# 8bit_ALU.net
KiCad netlist of a schematic drawn in EAGLE
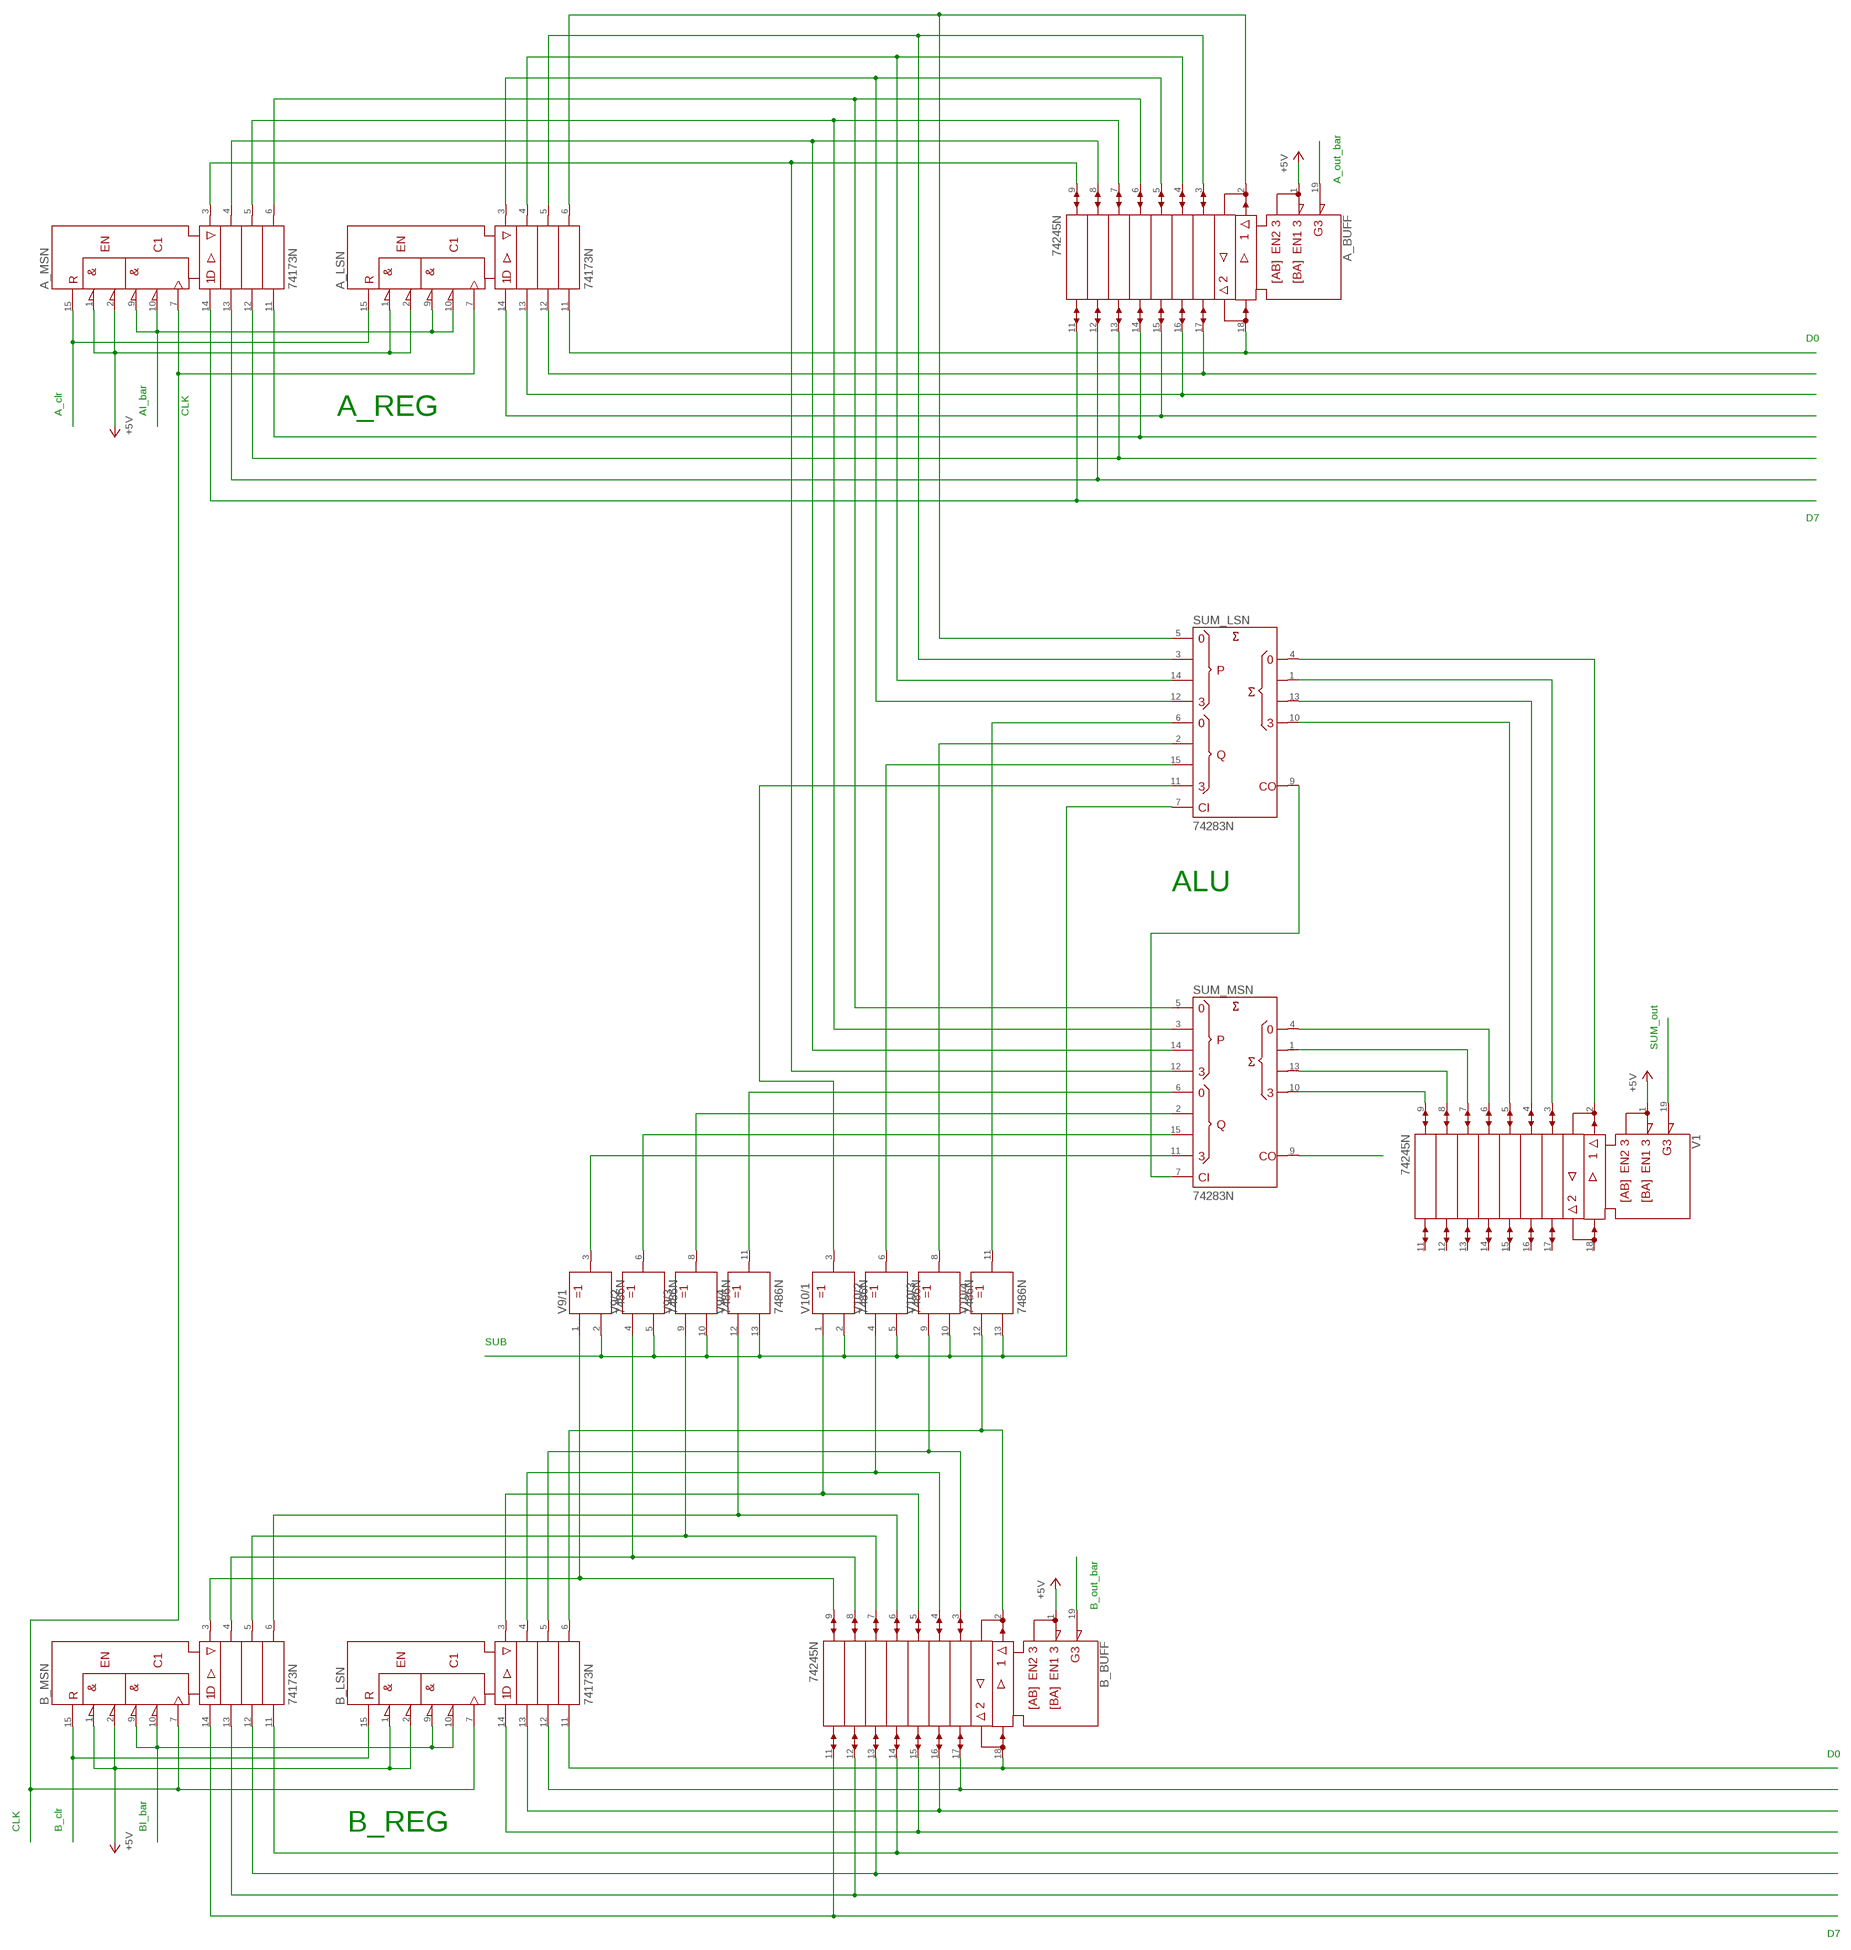
[diagram p0: schematic, sheet 1]

(export (version "E")
  (design (tool "Eeschema 10.0.6"))
  (components
    (comp (ref "A_BUFF")
      (value "74245N")
      (footprint "eagle-import:DIL20")
      (libsource (lib "eagle-import") (part "74245N"))
    )
    (comp (ref "A_LSN")
      (value "74173N")
      (footprint "eagle-import:DIL16")
      (libsource (lib "eagle-import") (part "74173N"))
    )
    (comp (ref "A_MSN")
      (value "74173N")
      (footprint "eagle-import:DIL16")
      (libsource (lib "eagle-import") (part "74173N"))
    )
    (comp (ref "B_BUFF")
      (value "74245N")
      (footprint "eagle-import:DIL20")
      (libsource (lib "eagle-import") (part "74245N"))
    )
    (comp (ref "B_LSN")
      (value "74173N")
      (footprint "eagle-import:DIL16")
      (libsource (lib "eagle-import") (part "74173N"))
    )
    (comp (ref "B_MSN")
      (value "74173N")
      (footprint "eagle-import:DIL16")
      (libsource (lib "eagle-import") (part "74173N"))
    )
    (comp (ref "SUM_LSN")
      (value "74283N")
      (footprint "eagle-import:DIL16")
      (libsource (lib "eagle-import") (part "74283N"))
    )
    (comp (ref "SUM_MSN")
      (value "74283N")
      (footprint "eagle-import:DIL16")
      (libsource (lib "eagle-import") (part "74283N"))
    )
    (comp (ref "V1")
      (value "74245N")
      (footprint "eagle-import:DIL20")
      (libsource (lib "eagle-import") (part "74245N"))
    )
    (comp (ref "V9")
      (value "7486N")
      (footprint "eagle-import:DIL14")
      (libsource (lib "eagle-import") (part "7486N"))
    )
    (comp (ref "V10")
      (value "7486N")
      (footprint "eagle-import:DIL14")
      (libsource (lib "eagle-import") (part "7486N"))
    )
  )
  (nets
    (net (code "1") (name "+5V") (class "Default")
      (node (ref "A_BUFF") (pin "1") (pinfunction "DIR_1") (pintype "input"))
      (node (ref "A_LSN") (pin "1") (pinfunction "M_1") (pintype "input"))
      (node (ref "A_LSN") (pin "2") (pinfunction "N_2") (pintype "input"))
      (node (ref "A_MSN") (pin "1") (pinfunction "M_1") (pintype "input"))
      (node (ref "A_MSN") (pin "2") (pinfunction "N_2") (pintype "input"))
      (node (ref "B_BUFF") (pin "1") (pinfunction "DIR_1") (pintype "input"))
      (node (ref "B_LSN") (pin "1") (pinfunction "M_1") (pintype "input"))
      (node (ref "B_LSN") (pin "2") (pinfunction "N_2") (pintype "input"))
      (node (ref "B_MSN") (pin "1") (pinfunction "M_1") (pintype "input"))
      (node (ref "B_MSN") (pin "2") (pinfunction "N_2") (pintype "input"))
      (node (ref "V1") (pin "1") (pinfunction "DIR_1") (pintype "input"))
    )
    (net (code "2") (name "Net-(A_BUFFC-A1)") (class "Default")
      (node (ref "A_BUFF") (pin "2") (pinfunction "A1_2") (pintype "bidirectional"))
      (node (ref "A_LSN") (pin "6") (pinfunction "4Q_6") (pintype "tri_state"))
      (node (ref "SUM_LSN") (pin "5") (pinfunction "A1_5") (pintype "input"))
    )
    (net (code "3") (name "Net-(A_BUFFC-A2)") (class "Default")
      (node (ref "A_BUFF") (pin "3") (pinfunction "A2_3") (pintype "bidirectional"))
      (node (ref "A_LSN") (pin "5") (pinfunction "3Q_5") (pintype "tri_state"))
      (node (ref "SUM_LSN") (pin "3") (pinfunction "A2_3") (pintype "input"))
    )
    (net (code "4") (name "Net-(A_BUFFC-A3)") (class "Default")
      (node (ref "A_BUFF") (pin "4") (pinfunction "A3_4") (pintype "bidirectional"))
      (node (ref "A_LSN") (pin "4") (pinfunction "2Q_4") (pintype "tri_state"))
      (node (ref "SUM_LSN") (pin "14") (pinfunction "A3_14") (pintype "input"))
    )
    (net (code "5") (name "Net-(A_BUFFC-A4)") (class "Default")
      (node (ref "A_BUFF") (pin "5") (pinfunction "A4_5") (pintype "bidirectional"))
      (node (ref "A_LSN") (pin "3") (pinfunction "1Q_3") (pintype "tri_state"))
      (node (ref "SUM_LSN") (pin "12") (pinfunction "A4_12") (pintype "input"))
    )
    (net (code "6") (name "Net-(A_BUFFC-A5)") (class "Default")
      (node (ref "A_BUFF") (pin "6") (pinfunction "A5_6") (pintype "bidirectional"))
      (node (ref "A_MSN") (pin "6") (pinfunction "4Q_6") (pintype "tri_state"))
      (node (ref "SUM_MSN") (pin "5") (pinfunction "A1_5") (pintype "input"))
    )
    (net (code "7") (name "Net-(A_BUFFC-A6)") (class "Default")
      (node (ref "A_BUFF") (pin "7") (pinfunction "A6_7") (pintype "bidirectional"))
      (node (ref "A_MSN") (pin "5") (pinfunction "3Q_5") (pintype "tri_state"))
      (node (ref "SUM_MSN") (pin "3") (pinfunction "A2_3") (pintype "input"))
    )
    (net (code "8") (name "Net-(A_BUFFC-A7)") (class "Default")
      (node (ref "A_BUFF") (pin "8") (pinfunction "A7_8") (pintype "bidirectional"))
      (node (ref "A_MSN") (pin "4") (pinfunction "2Q_4") (pintype "tri_state"))
      (node (ref "SUM_MSN") (pin "14") (pinfunction "A3_14") (pintype "input"))
    )
    (net (code "9") (name "Net-(A_BUFFC-A8)") (class "Default")
      (node (ref "A_BUFF") (pin "9") (pinfunction "A8_9") (pintype "bidirectional"))
      (node (ref "A_MSN") (pin "3") (pinfunction "1Q_3") (pintype "tri_state"))
      (node (ref "SUM_MSN") (pin "12") (pinfunction "A4_12") (pintype "input"))
    )
    (net (code "10") (name "Net-(A_BUFFC-B1)") (class "Default")
      (node (ref "A_BUFF") (pin "18") (pinfunction "B1_18") (pintype "bidirectional"))
      (node (ref "A_LSN") (pin "11") (pinfunction "4D_11") (pintype "input"))
    )
    (net (code "11") (name "Net-(A_BUFFC-B2)") (class "Default")
      (node (ref "A_BUFF") (pin "17") (pinfunction "B2_17") (pintype "bidirectional"))
      (node (ref "A_LSN") (pin "12") (pinfunction "3D_12") (pintype "input"))
    )
    (net (code "12") (name "Net-(A_BUFFC-B3)") (class "Default")
      (node (ref "A_BUFF") (pin "16") (pinfunction "B3_16") (pintype "bidirectional"))
      (node (ref "A_LSN") (pin "13") (pinfunction "2D_13") (pintype "input"))
    )
    (net (code "13") (name "Net-(A_BUFFC-B4)") (class "Default")
      (node (ref "A_BUFF") (pin "15") (pinfunction "B4_15") (pintype "bidirectional"))
      (node (ref "A_LSN") (pin "14") (pinfunction "1D_14") (pintype "input"))
    )
    (net (code "14") (name "Net-(A_BUFFC-B5)") (class "Default")
      (node (ref "A_BUFF") (pin "14") (pinfunction "B5_14") (pintype "bidirectional"))
      (node (ref "A_MSN") (pin "11") (pinfunction "4D_11") (pintype "input"))
    )
    (net (code "15") (name "Net-(A_BUFFC-B6)") (class "Default")
      (node (ref "A_BUFF") (pin "13") (pinfunction "B6_13") (pintype "bidirectional"))
      (node (ref "A_MSN") (pin "12") (pinfunction "3D_12") (pintype "input"))
    )
    (net (code "16") (name "Net-(A_BUFFC-B7)") (class "Default")
      (node (ref "A_BUFF") (pin "12") (pinfunction "B7_12") (pintype "bidirectional"))
      (node (ref "A_MSN") (pin "13") (pinfunction "2D_13") (pintype "input"))
    )
    (net (code "17") (name "Net-(A_BUFFC-B8)") (class "Default")
      (node (ref "A_BUFF") (pin "11") (pinfunction "B8_11") (pintype "bidirectional"))
      (node (ref "A_MSN") (pin "14") (pinfunction "1D_14") (pintype "input"))
    )
    (net (code "18") (name "Net-(A_LSNC-CLK)") (class "Default")
      (node (ref "A_LSN") (pin "7") (pinfunction "CLK_7") (pintype "input"))
      (node (ref "A_MSN") (pin "7") (pinfunction "CLK_7") (pintype "input"))
      (node (ref "B_LSN") (pin "7") (pinfunction "CLK_7") (pintype "input"))
      (node (ref "B_MSN") (pin "7") (pinfunction "CLK_7") (pintype "input"))
    )
    (net (code "19") (name "Net-(A_LSNC-CLR)") (class "Default")
      (node (ref "A_LSN") (pin "15") (pinfunction "CLR_15") (pintype "input"))
      (node (ref "A_MSN") (pin "15") (pinfunction "CLR_15") (pintype "input"))
    )
    (net (code "20") (name "Net-(A_LSNC-~{G1})") (class "Default")
      (node (ref "A_LSN") (pin "10") (pinfunction "~{G2}_10") (pintype "input"))
      (node (ref "A_LSN") (pin "9") (pinfunction "~{G1}_9") (pintype "input"))
      (node (ref "A_MSN") (pin "10") (pinfunction "~{G2}_10") (pintype "input"))
      (node (ref "A_MSN") (pin "9") (pinfunction "~{G1}_9") (pintype "input"))
    )
    (net (code "21") (name "Net-(B_BUFFC-A1)") (class "Default")
      (node (ref "B_BUFF") (pin "2") (pinfunction "A1_2") (pintype "bidirectional"))
      (node (ref "B_LSN") (pin "6") (pinfunction "4Q_6") (pintype "tri_state"))
      (node (ref "V10") (pin "12") (pinfunction "A_12") (pintype "input"))
    )
    (net (code "22") (name "Net-(B_BUFFC-A2)") (class "Default")
      (node (ref "B_BUFF") (pin "3") (pinfunction "A2_3") (pintype "bidirectional"))
      (node (ref "B_LSN") (pin "5") (pinfunction "3Q_5") (pintype "tri_state"))
      (node (ref "V10") (pin "9") (pinfunction "A_9") (pintype "input"))
    )
    (net (code "23") (name "Net-(B_BUFFC-A3)") (class "Default")
      (node (ref "B_BUFF") (pin "4") (pinfunction "A3_4") (pintype "bidirectional"))
      (node (ref "B_LSN") (pin "4") (pinfunction "2Q_4") (pintype "tri_state"))
      (node (ref "V10") (pin "4") (pinfunction "A_4") (pintype "input"))
    )
    (net (code "24") (name "Net-(B_BUFFC-A4)") (class "Default")
      (node (ref "B_BUFF") (pin "5") (pinfunction "A4_5") (pintype "bidirectional"))
      (node (ref "B_LSN") (pin "3") (pinfunction "1Q_3") (pintype "tri_state"))
      (node (ref "V10") (pin "1") (pinfunction "A_1") (pintype "input"))
    )
    (net (code "25") (name "Net-(B_BUFFC-A5)") (class "Default")
      (node (ref "B_BUFF") (pin "6") (pinfunction "A5_6") (pintype "bidirectional"))
      (node (ref "B_MSN") (pin "6") (pinfunction "4Q_6") (pintype "tri_state"))
      (node (ref "V9") (pin "12") (pinfunction "A_12") (pintype "input"))
    )
    (net (code "26") (name "Net-(B_BUFFC-A6)") (class "Default")
      (node (ref "B_BUFF") (pin "7") (pinfunction "A6_7") (pintype "bidirectional"))
      (node (ref "B_MSN") (pin "5") (pinfunction "3Q_5") (pintype "tri_state"))
      (node (ref "V9") (pin "9") (pinfunction "A_9") (pintype "input"))
    )
    (net (code "27") (name "Net-(B_BUFFC-A7)") (class "Default")
      (node (ref "B_BUFF") (pin "8") (pinfunction "A7_8") (pintype "bidirectional"))
      (node (ref "B_MSN") (pin "4") (pinfunction "2Q_4") (pintype "tri_state"))
      (node (ref "V9") (pin "4") (pinfunction "A_4") (pintype "input"))
    )
    (net (code "28") (name "Net-(B_BUFFC-A8)") (class "Default")
      (node (ref "B_BUFF") (pin "9") (pinfunction "A8_9") (pintype "bidirectional"))
      (node (ref "B_MSN") (pin "3") (pinfunction "1Q_3") (pintype "tri_state"))
      (node (ref "V9") (pin "1") (pinfunction "A_1") (pintype "input"))
    )
    (net (code "29") (name "Net-(B_BUFFC-B1)") (class "Default")
      (node (ref "B_BUFF") (pin "18") (pinfunction "B1_18") (pintype "bidirectional"))
      (node (ref "B_LSN") (pin "11") (pinfunction "4D_11") (pintype "input"))
    )
    (net (code "30") (name "Net-(B_BUFFC-B2)") (class "Default")
      (node (ref "B_BUFF") (pin "17") (pinfunction "B2_17") (pintype "bidirectional"))
      (node (ref "B_LSN") (pin "12") (pinfunction "3D_12") (pintype "input"))
    )
    (net (code "31") (name "Net-(B_BUFFC-B3)") (class "Default")
      (node (ref "B_BUFF") (pin "16") (pinfunction "B3_16") (pintype "bidirectional"))
      (node (ref "B_LSN") (pin "13") (pinfunction "2D_13") (pintype "input"))
    )
    (net (code "32") (name "Net-(B_BUFFC-B4)") (class "Default")
      (node (ref "B_BUFF") (pin "15") (pinfunction "B4_15") (pintype "bidirectional"))
      (node (ref "B_LSN") (pin "14") (pinfunction "1D_14") (pintype "input"))
    )
    (net (code "33") (name "Net-(B_BUFFC-B5)") (class "Default")
      (node (ref "B_BUFF") (pin "14") (pinfunction "B5_14") (pintype "bidirectional"))
      (node (ref "B_MSN") (pin "11") (pinfunction "4D_11") (pintype "input"))
    )
    (net (code "34") (name "Net-(B_BUFFC-B6)") (class "Default")
      (node (ref "B_BUFF") (pin "13") (pinfunction "B6_13") (pintype "bidirectional"))
      (node (ref "B_MSN") (pin "12") (pinfunction "3D_12") (pintype "input"))
    )
    (net (code "35") (name "Net-(B_BUFFC-B7)") (class "Default")
      (node (ref "B_BUFF") (pin "12") (pinfunction "B7_12") (pintype "bidirectional"))
      (node (ref "B_MSN") (pin "13") (pinfunction "2D_13") (pintype "input"))
    )
    (net (code "36") (name "Net-(B_BUFFC-B8)") (class "Default")
      (node (ref "B_BUFF") (pin "11") (pinfunction "B8_11") (pintype "bidirectional"))
      (node (ref "B_MSN") (pin "14") (pinfunction "1D_14") (pintype "input"))
    )
    (net (code "37") (name "Net-(B_LSNC-CLR)") (class "Default")
      (node (ref "B_LSN") (pin "15") (pinfunction "CLR_15") (pintype "input"))
      (node (ref "B_MSN") (pin "15") (pinfunction "CLR_15") (pintype "input"))
    )
    (net (code "38") (name "Net-(B_LSNC-~{G1})") (class "Default")
      (node (ref "B_LSN") (pin "10") (pinfunction "~{G2}_10") (pintype "input"))
      (node (ref "B_LSN") (pin "9") (pinfunction "~{G1}_9") (pintype "input"))
      (node (ref "B_MSN") (pin "10") (pinfunction "~{G2}_10") (pintype "input"))
      (node (ref "B_MSN") (pin "9") (pinfunction "~{G1}_9") (pintype "input"))
    )
    (net (code "39") (name "Net-(SUM_LSNC-B1)") (class "Default")
      (node (ref "SUM_LSN") (pin "6") (pinfunction "B1_6") (pintype "input"))
      (node (ref "V10") (pin "11") (pinfunction "Y_11") (pintype "output"))
    )
    (net (code "40") (name "Net-(SUM_LSNC-B2)") (class "Default")
      (node (ref "SUM_LSN") (pin "2") (pinfunction "B2_2") (pintype "input"))
      (node (ref "V10") (pin "8") (pinfunction "Y_8") (pintype "output"))
    )
    (net (code "41") (name "Net-(SUM_LSNC-B3)") (class "Default")
      (node (ref "SUM_LSN") (pin "15") (pinfunction "B3_15") (pintype "input"))
      (node (ref "V10") (pin "6") (pinfunction "Y_6") (pintype "output"))
    )
    (net (code "42") (name "Net-(SUM_LSNC-B4)") (class "Default")
      (node (ref "SUM_LSN") (pin "11") (pinfunction "B4_11") (pintype "input"))
      (node (ref "V10") (pin "3") (pinfunction "Y_3") (pintype "output"))
    )
    (net (code "43") (name "Net-(SUM_LSNC-C0)") (class "Default")
      (node (ref "SUM_LSN") (pin "7") (pinfunction "C0_7") (pintype "input"))
      (node (ref "V10") (pin "10") (pinfunction "B_10") (pintype "input"))
      (node (ref "V10") (pin "13") (pinfunction "B_13") (pintype "input"))
      (node (ref "V10") (pin "2") (pinfunction "B_2") (pintype "input"))
      (node (ref "V10") (pin "5") (pinfunction "B_5") (pintype "input"))
      (node (ref "V9") (pin "10") (pinfunction "B_10") (pintype "input"))
      (node (ref "V9") (pin "13") (pinfunction "B_13") (pintype "input"))
      (node (ref "V9") (pin "2") (pinfunction "B_2") (pintype "input"))
      (node (ref "V9") (pin "5") (pinfunction "B_5") (pintype "input"))
    )
    (net (code "44") (name "Net-(SUM_LSNC-C4)") (class "Default")
      (node (ref "SUM_LSN") (pin "9") (pinfunction "C4_9") (pintype "output"))
      (node (ref "SUM_MSN") (pin "7") (pinfunction "C0_7") (pintype "input"))
    )
    (net (code "45") (name "Net-(SUM_LSNC-S1)") (class "Default")
      (node (ref "SUM_LSN") (pin "4") (pinfunction "S1_4") (pintype "output"))
      (node (ref "V1") (pin "2") (pinfunction "A1_2") (pintype "bidirectional"))
    )
    (net (code "46") (name "Net-(SUM_LSNC-S2)") (class "Default")
      (node (ref "SUM_LSN") (pin "1") (pinfunction "S2_1") (pintype "output"))
      (node (ref "V1") (pin "3") (pinfunction "A2_3") (pintype "bidirectional"))
    )
    (net (code "47") (name "Net-(SUM_LSNC-S3)") (class "Default")
      (node (ref "SUM_LSN") (pin "13") (pinfunction "S3_13") (pintype "output"))
      (node (ref "V1") (pin "4") (pinfunction "A3_4") (pintype "bidirectional"))
    )
    (net (code "48") (name "Net-(SUM_LSNC-S4)") (class "Default")
      (node (ref "SUM_LSN") (pin "10") (pinfunction "S4_10") (pintype "output"))
      (node (ref "V1") (pin "5") (pinfunction "A4_5") (pintype "bidirectional"))
    )
    (net (code "49") (name "Net-(SUM_MSNC-B1)") (class "Default")
      (node (ref "SUM_MSN") (pin "6") (pinfunction "B1_6") (pintype "input"))
      (node (ref "V9") (pin "11") (pinfunction "Y_11") (pintype "output"))
    )
    (net (code "50") (name "Net-(SUM_MSNC-B2)") (class "Default")
      (node (ref "SUM_MSN") (pin "2") (pinfunction "B2_2") (pintype "input"))
      (node (ref "V9") (pin "8") (pinfunction "Y_8") (pintype "output"))
    )
    (net (code "51") (name "Net-(SUM_MSNC-B3)") (class "Default")
      (node (ref "SUM_MSN") (pin "15") (pinfunction "B3_15") (pintype "input"))
      (node (ref "V9") (pin "6") (pinfunction "Y_6") (pintype "output"))
    )
    (net (code "52") (name "Net-(SUM_MSNC-B4)") (class "Default")
      (node (ref "SUM_MSN") (pin "11") (pinfunction "B4_11") (pintype "input"))
      (node (ref "V9") (pin "3") (pinfunction "Y_3") (pintype "output"))
    )
    (net (code "53") (name "Net-(SUM_MSNC-S1)") (class "Default")
      (node (ref "SUM_MSN") (pin "4") (pinfunction "S1_4") (pintype "output"))
      (node (ref "V1") (pin "6") (pinfunction "A5_6") (pintype "bidirectional"))
    )
    (net (code "54") (name "Net-(SUM_MSNC-S2)") (class "Default")
      (node (ref "SUM_MSN") (pin "1") (pinfunction "S2_1") (pintype "output"))
      (node (ref "V1") (pin "7") (pinfunction "A6_7") (pintype "bidirectional"))
    )
    (net (code "55") (name "Net-(SUM_MSNC-S3)") (class "Default")
      (node (ref "SUM_MSN") (pin "13") (pinfunction "S3_13") (pintype "output"))
      (node (ref "V1") (pin "8") (pinfunction "A7_8") (pintype "bidirectional"))
    )
    (net (code "56") (name "Net-(SUM_MSNC-S4)") (class "Default")
      (node (ref "SUM_MSN") (pin "10") (pinfunction "S4_10") (pintype "output"))
      (node (ref "V1") (pin "9") (pinfunction "A8_9") (pintype "bidirectional"))
    )
    (net (code "57") (name "unconnected-(A_BUFFC-~{G}-Pad19)") (class "Default")
      (node (ref "A_BUFF") (pin "19") (pinfunction "~{G}_19") (pintype "input"))
    )
    (net (code "58") (name "unconnected-(B_BUFFC-~{G}-Pad19)") (class "Default")
      (node (ref "B_BUFF") (pin "19") (pinfunction "~{G}_19") (pintype "input"))
    )
    (net (code "59") (name "unconnected-(SUM_MSNC-C4-Pad9)") (class "Default")
      (node (ref "SUM_MSN") (pin "9") (pinfunction "C4_9") (pintype "output"))
    )
    (net (code "60") (name "unconnected-(V1C-B1-Pad18)") (class "Default")
      (node (ref "V1") (pin "18") (pinfunction "B1_18") (pintype "bidirectional"))
    )
    (net (code "61") (name "unconnected-(V1C-B2-Pad17)") (class "Default")
      (node (ref "V1") (pin "17") (pinfunction "B2_17") (pintype "bidirectional"))
    )
    (net (code "62") (name "unconnected-(V1C-B3-Pad16)") (class "Default")
      (node (ref "V1") (pin "16") (pinfunction "B3_16") (pintype "bidirectional"))
    )
    (net (code "63") (name "unconnected-(V1C-B4-Pad15)") (class "Default")
      (node (ref "V1") (pin "15") (pinfunction "B4_15") (pintype "bidirectional"))
    )
    (net (code "64") (name "unconnected-(V1C-B5-Pad14)") (class "Default")
      (node (ref "V1") (pin "14") (pinfunction "B5_14") (pintype "bidirectional"))
    )
    (net (code "65") (name "unconnected-(V1C-B6-Pad13)") (class "Default")
      (node (ref "V1") (pin "13") (pinfunction "B6_13") (pintype "bidirectional"))
    )
    (net (code "66") (name "unconnected-(V1C-B7-Pad12)") (class "Default")
      (node (ref "V1") (pin "12") (pinfunction "B7_12") (pintype "bidirectional"))
    )
    (net (code "67") (name "unconnected-(V1C-B8-Pad11)") (class "Default")
      (node (ref "V1") (pin "11") (pinfunction "B8_11") (pintype "bidirectional"))
    )
    (net (code "68") (name "unconnected-(V1C-~{G}-Pad19)") (class "Default")
      (node (ref "V1") (pin "19") (pinfunction "~{G}_19") (pintype "input"))
    )
  )
)
